# SCH_battery_controller_2026-03-11.net
KiCad netlist of a schematic drawn in EasyEDA
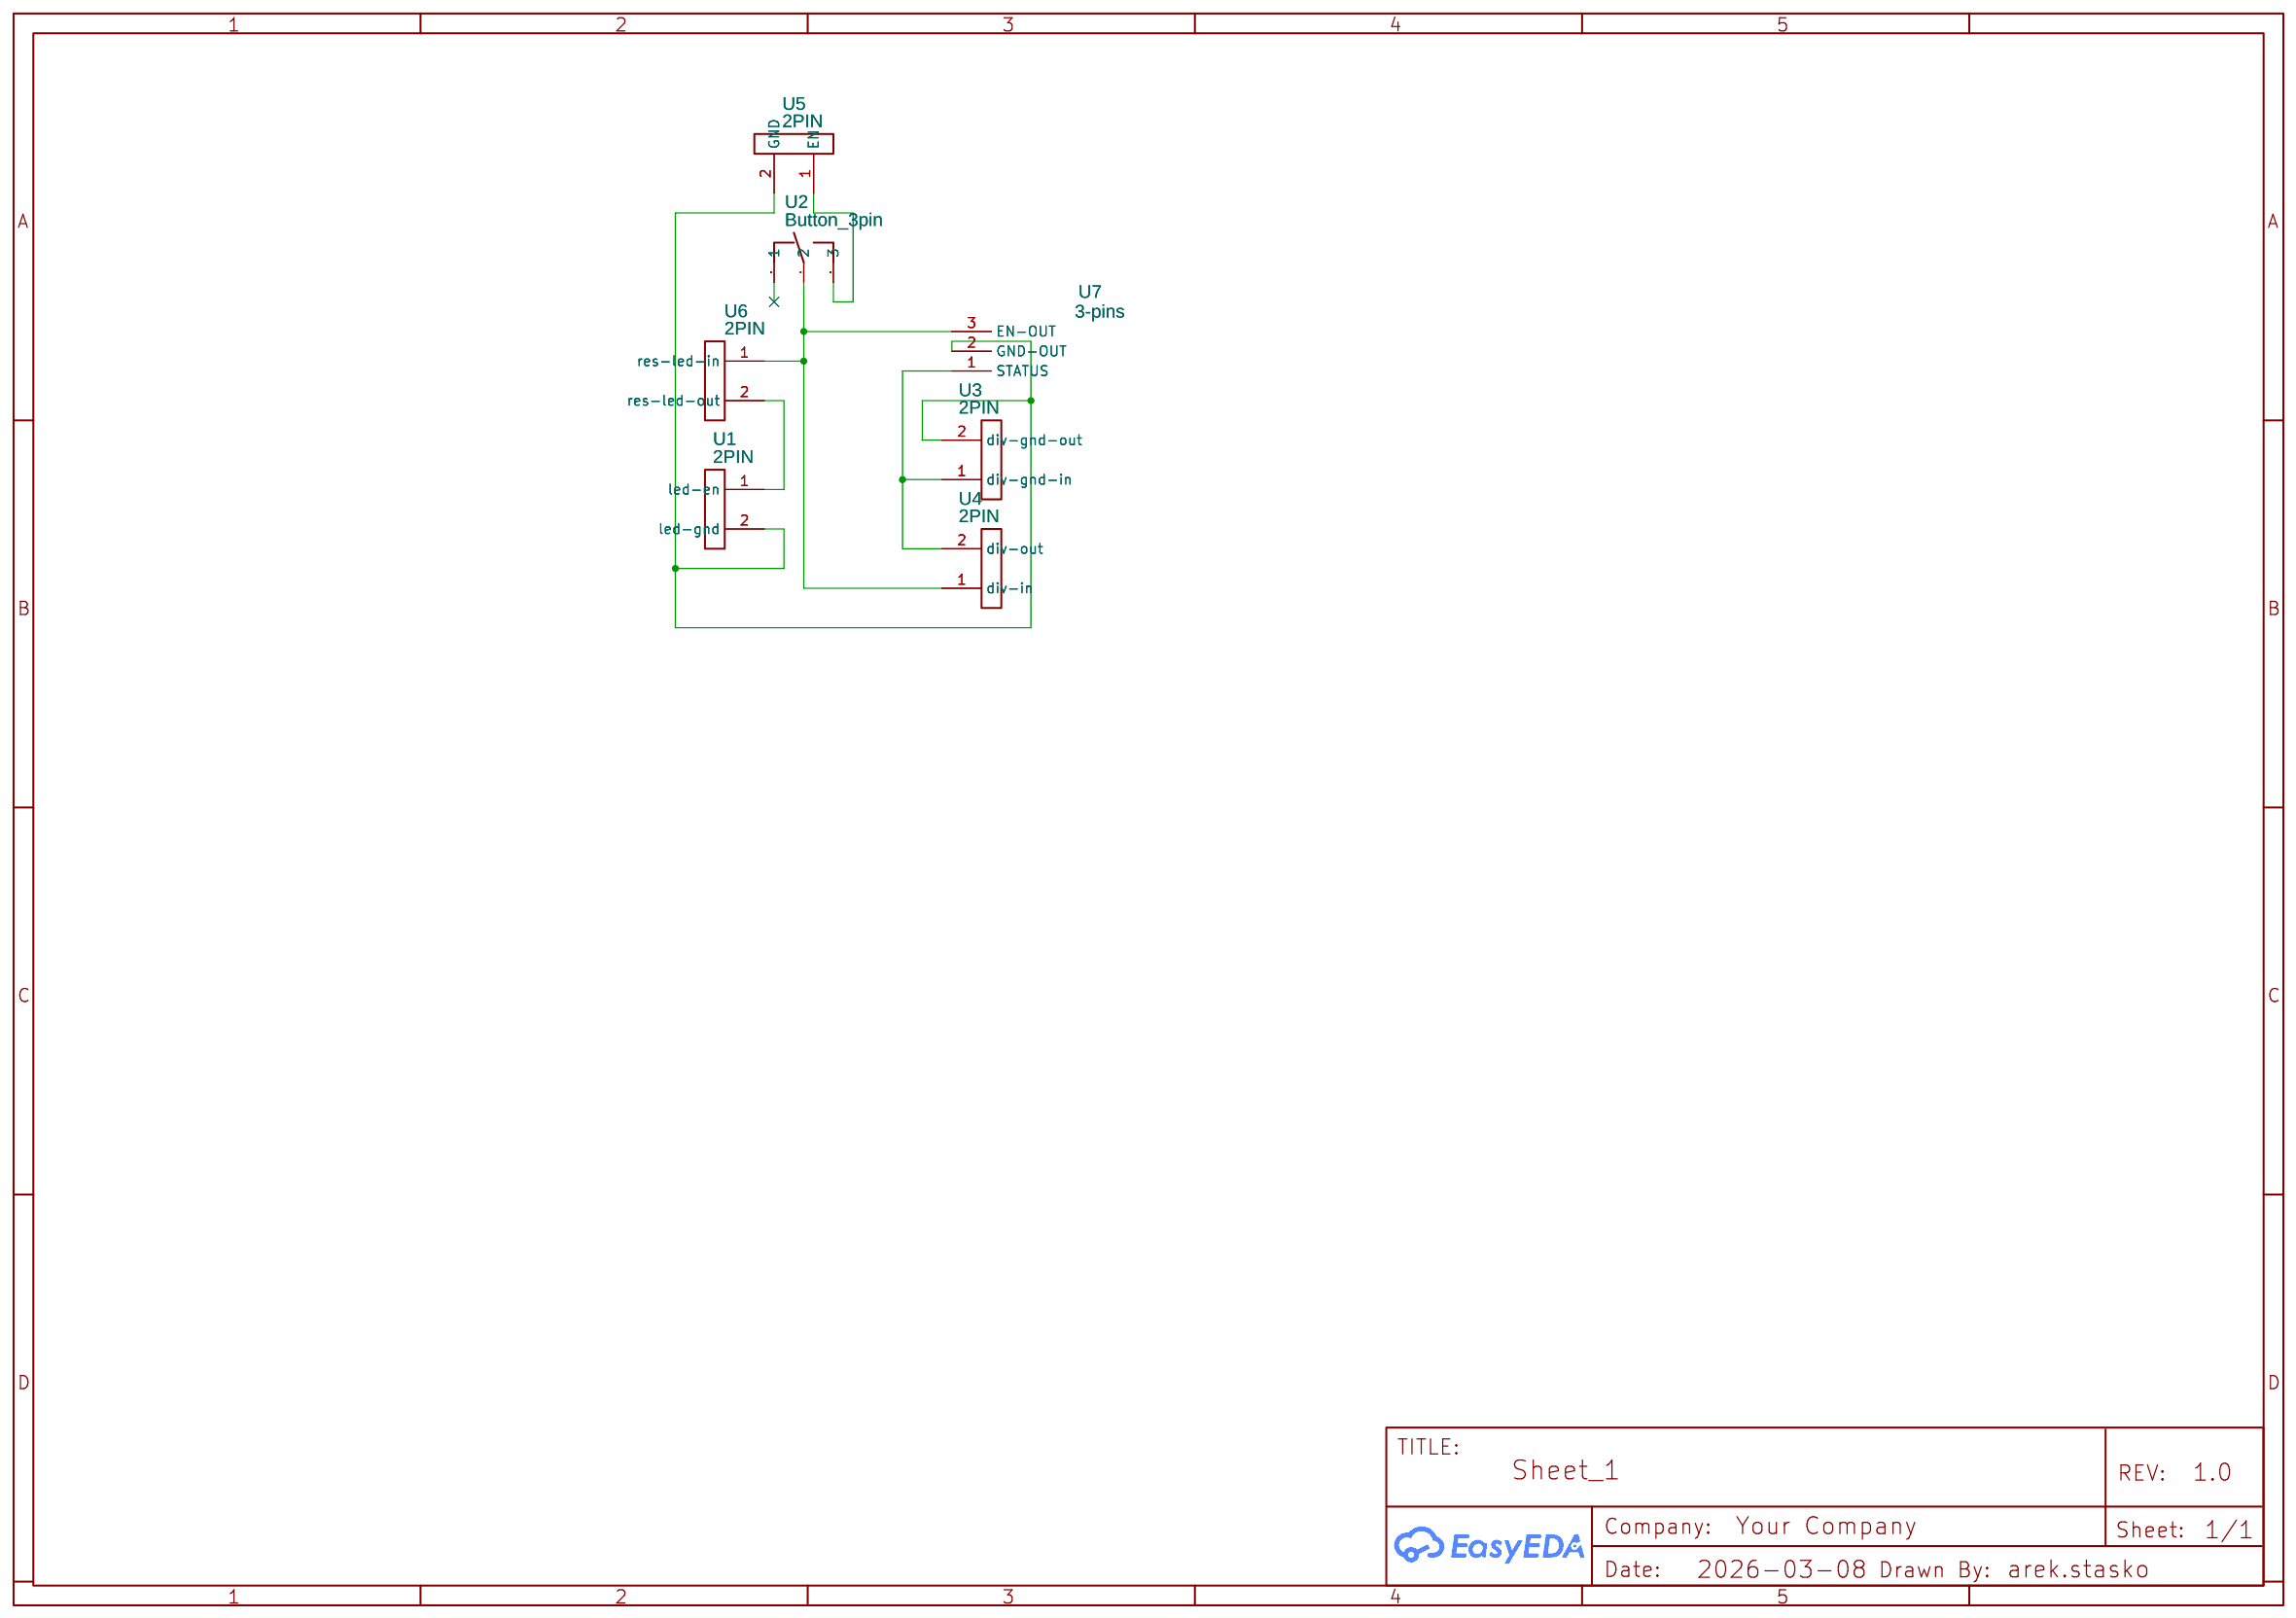
[diagram p0: schematic sheet]

(export (version "E")
  (design (tool "Eeschema 10.0.6"))
  (components
    (comp (ref "U1") (value "2PIN") (libsource (lib "") (part "2PIN_2")))
    (comp (ref "U2") (value "Button_3pin") (libsource (lib "") (part "Button_3pin")))
    (comp (ref "U3") (value "2PIN") (libsource (lib "") (part "2PIN")))
    (comp (ref "U4") (value "2PIN") (libsource (lib "") (part "2PIN_3")))
    (comp (ref "U5") (value "2PIN") (libsource (lib "") (part "2PIN_4")))
    (comp (ref "U6") (value "2PIN") (libsource (lib "") (part "2PIN_1")))
    (comp (ref "U7") (value "3-pins") (libsource (lib "") (part "3-pins")))
  )
  (nets
    (net (code "1") (name "Net-(U1-led-en)") (class "Default")
      (node (ref "U1") (pin "1") (pinfunction "led-en_1") (pintype "unspecified"))
      (node (ref "U6") (pin "2") (pinfunction "res-led-out_2") (pintype "unspecified"))
    )
    (net (code "2") (name "Net-(U1-led-gnd)") (class "Default")
      (node (ref "U1") (pin "2") (pinfunction "led-gnd_2") (pintype "unspecified"))
      (node (ref "U3") (pin "2") (pinfunction "div-gnd-out_2") (pintype "unspecified"))
      (node (ref "U5") (pin "2") (pinfunction "GND_2") (pintype "unspecified"))
      (node (ref "U7") (pin "2") (pinfunction "GND-OUT_2") (pintype "unspecified"))
    )
    (net (code "3") (name "Net-(U3-div-gnd-in)") (class "Default")
      (node (ref "U3") (pin "1") (pinfunction "div-gnd-in_1") (pintype "unspecified"))
      (node (ref "U4") (pin "2") (pinfunction "div-out_2") (pintype "unspecified"))
      (node (ref "U7") (pin "1") (pinfunction "STATUS_1") (pintype "unspecified"))
    )
    (net (code "4") (name "Net-(U4-div-in)") (class "Default")
      (node (ref "U2") (pin "2") (pinfunction "2_2") (pintype "unspecified"))
      (node (ref "U4") (pin "1") (pinfunction "div-in_1") (pintype "unspecified"))
      (node (ref "U6") (pin "1") (pinfunction "res-led-in_1") (pintype "unspecified"))
      (node (ref "U7") (pin "3") (pinfunction "EN-OUT_3") (pintype "unspecified"))
    )
    (net (code "5") (name "Net-(U5-EN)") (class "Default")
      (node (ref "U2") (pin "3") (pinfunction "3_3") (pintype "unspecified"))
      (node (ref "U5") (pin "1") (pinfunction "EN_1") (pintype "unspecified"))
    )
    (net (code "6") (name "unconnected-(U2-Pad1)") (class "Default")
      (node (ref "U2") (pin "1") (pinfunction "1_1") (pintype "unspecified+no_connect"))
    )
  )
)
